# Connectivity_V2.net
KiCad netlist of a schematic drawn in Altium Designer
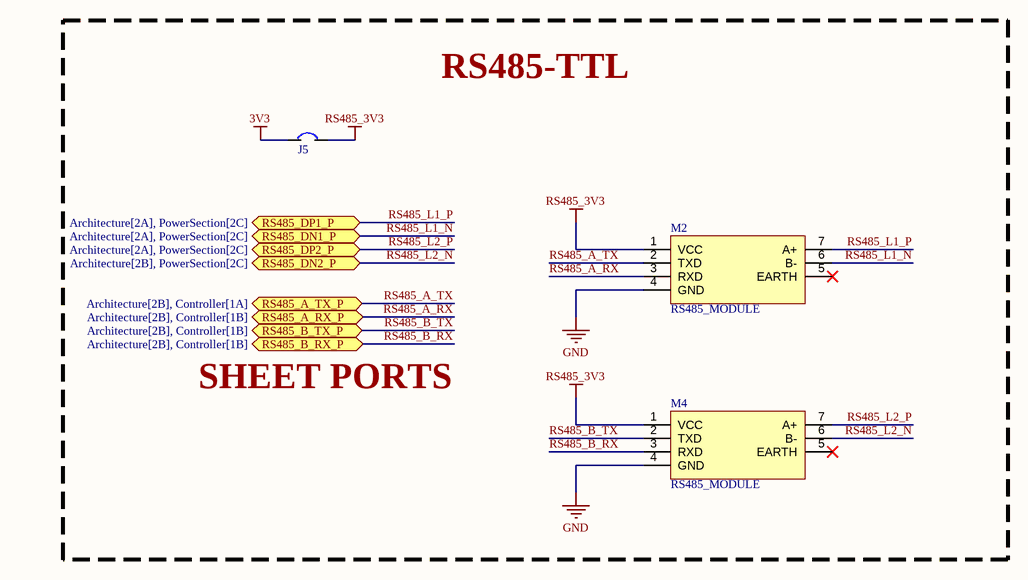
[diagram p0: Connectivity_V2.SchDoc]

(export (version "E")
  (design (tool "Eeschema 10.0.6"))
  (components
    (comp (ref "J5")
      (value "Jumper_2P")
      (footprint "Jumper_2P")
      (description "Jumper 2 Pins")
      (libsource (lib "Jumper") (part "Jumper_2P"))
    )
    (comp (ref "M2")
      (value "RS485_MODULE")
      (footprint "TTL-RS485")
      (description "TTL-RS485")
      (fields (field (name "Comment") "ERP_140-3"))
      (libsource (lib "WiredModule") (part "TTL-RS485"))
    )
    (comp (ref "M4")
      (value "RS485_MODULE")
      (footprint "TTL-RS485")
      (description "TTL-RS485")
      (fields (field (name "Comment") "ERP_140-3"))
      (libsource (lib "WiredModule") (part "TTL-RS485"))
    )
  )
  (nets
    (net (code "1") (name "/RS485_A_RX") (class "Default")
      (node (ref "M2") (pin "3") (pinfunction "RXD_3") (pintype "passive"))
    )
    (net (code "2") (name "/RS485_A_TX") (class "Default")
      (node (ref "M2") (pin "2") (pinfunction "TXD_2") (pintype "passive"))
    )
    (net (code "3") (name "/RS485_B_RX") (class "Default")
      (node (ref "M4") (pin "3") (pinfunction "RXD_3") (pintype "passive"))
    )
    (net (code "4") (name "/RS485_B_TX") (class "Default")
      (node (ref "M4") (pin "2") (pinfunction "TXD_2") (pintype "passive"))
    )
    (net (code "5") (name "/RS485_L1_N") (class "Default")
      (node (ref "M2") (pin "6") (pinfunction "B-_6") (pintype "passive"))
    )
    (net (code "6") (name "/RS485_L1_P") (class "Default")
      (node (ref "M2") (pin "7") (pinfunction "A+_7") (pintype "passive"))
    )
    (net (code "7") (name "/RS485_L2_N") (class "Default")
      (node (ref "M4") (pin "6") (pinfunction "B-_6") (pintype "passive"))
    )
    (net (code "8") (name "/RS485_L2_P") (class "Default")
      (node (ref "M4") (pin "7") (pinfunction "A+_7") (pintype "passive"))
    )
    (net (code "9") (name "3V3") (class "Default") (node (ref "J5") (pin "1") (pintype "passive")))
    (net (code "10") (name "GND") (class "Default")
      (node (ref "M2") (pin "4") (pinfunction "GND_4") (pintype "passive"))
      (node (ref "M4") (pin "4") (pinfunction "GND_4") (pintype "passive"))
    )
    (net (code "11") (name "RS485_3V3") (class "Default")
      (node (ref "J5") (pin "2") (pintype "passive"))
      (node (ref "M2") (pin "1") (pinfunction "VCC_1") (pintype "passive"))
      (node (ref "M4") (pin "1") (pinfunction "VCC_1") (pintype "passive"))
    )
    (net (code "12") (name "unconnected-(M2-EARTH-Pad5)") (class "Default")
      (node (ref "M2") (pin "5") (pinfunction "EARTH_5") (pintype "passive+no_connect"))
    )
    (net (code "13") (name "unconnected-(M4-EARTH-Pad5)") (class "Default")
      (node (ref "M4") (pin "5") (pinfunction "EARTH_5") (pintype "passive+no_connect"))
    )
  )
)
